# PCU_PCIe.net
KiCad netlist of a schematic drawn in Altium Designer
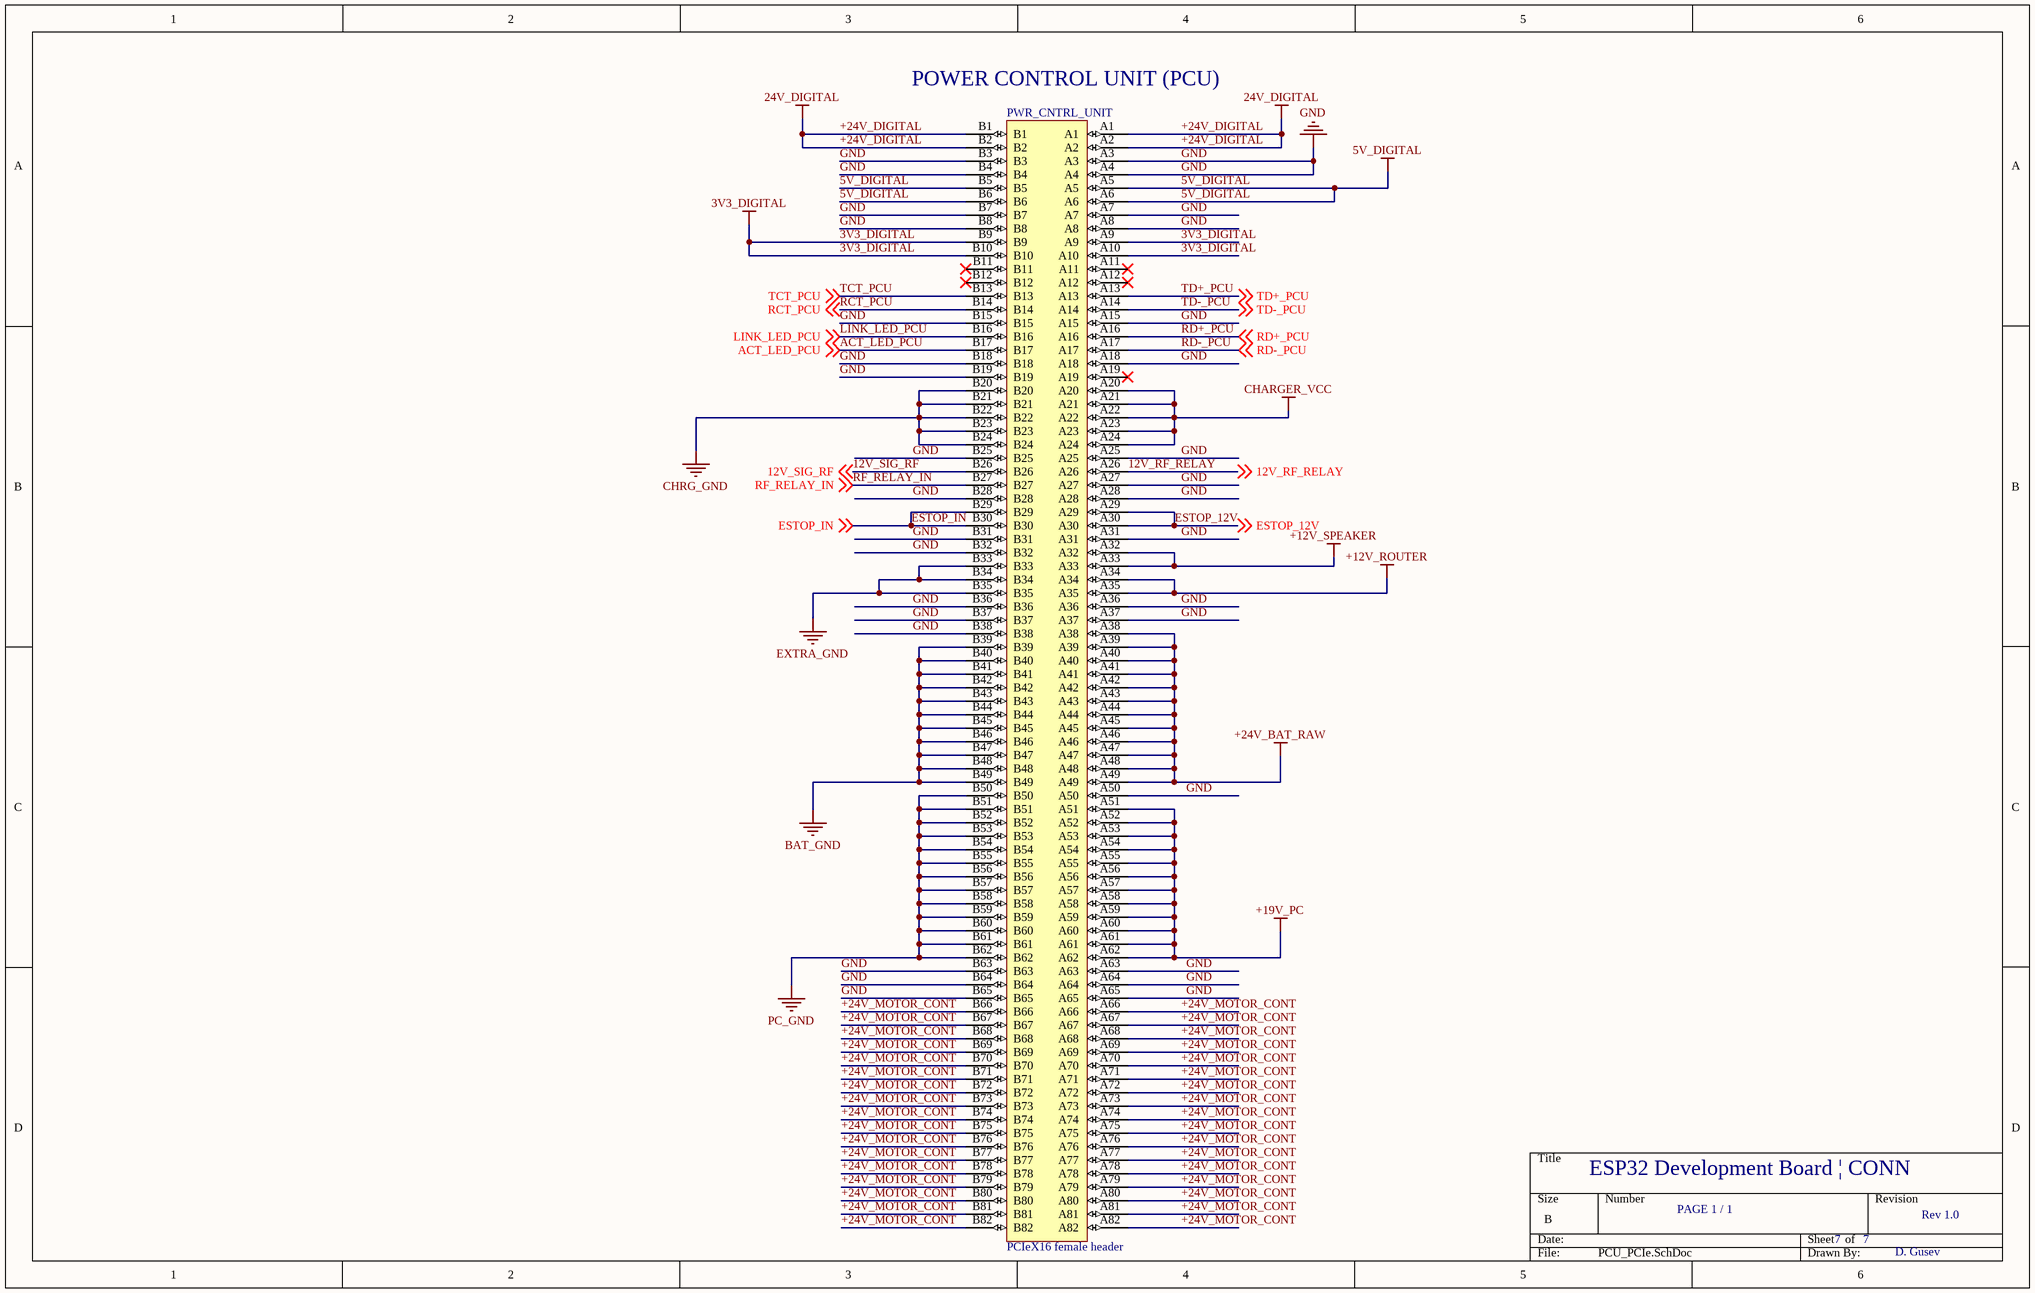
[diagram p0: PCU_PCIe.SchDoc]

(export (version "E")
  (design (tool "Eeschema 10.0.6"))
  (components
    (comp (ref "PWR_CNTRL_UNIT")
      (value "PCIeX16 female header")
      (footprint "SAMTEC_PCIE-164-02-X-D-TH")
      (description "164-position SAMTEC female header")
      (libsource (lib "ANTS-MotherBoard-B1") (part "PCIeX16 female header"))
    )
  )
  (nets
    (net (code "1") (name "+12V_ROUTER") (class "Default")
      (node (ref "PWR_CNTRL_UNIT") (pin "A34") (pinfunction "A34_A34") (pintype "bidirectional"))
      (node (ref "PWR_CNTRL_UNIT") (pin "A35") (pinfunction "A35_A35") (pintype "bidirectional"))
    )
    (net (code "2") (name "+12V_SPEAKER") (class "Default")
      (node (ref "PWR_CNTRL_UNIT") (pin "A32") (pinfunction "A32_A32") (pintype "bidirectional"))
      (node (ref "PWR_CNTRL_UNIT") (pin "A33") (pinfunction "A33_A33") (pintype "bidirectional"))
    )
    (net (code "3") (name "+19V_PC") (class "Default")
      (node (ref "PWR_CNTRL_UNIT") (pin "A51") (pinfunction "A51_A51") (pintype "bidirectional"))
      (node (ref "PWR_CNTRL_UNIT") (pin "A52") (pinfunction "A52_A52") (pintype "bidirectional"))
      (node (ref "PWR_CNTRL_UNIT") (pin "A53") (pinfunction "A53_A53") (pintype "bidirectional"))
      (node (ref "PWR_CNTRL_UNIT") (pin "A54") (pinfunction "A54_A54") (pintype "bidirectional"))
      (node (ref "PWR_CNTRL_UNIT") (pin "A55") (pinfunction "A55_A55") (pintype "bidirectional"))
      (node (ref "PWR_CNTRL_UNIT") (pin "A56") (pinfunction "A56_A56") (pintype "bidirectional"))
      (node (ref "PWR_CNTRL_UNIT") (pin "A57") (pinfunction "A57_A57") (pintype "bidirectional"))
      (node (ref "PWR_CNTRL_UNIT") (pin "A58") (pinfunction "A58_A58") (pintype "bidirectional"))
      (node (ref "PWR_CNTRL_UNIT") (pin "A59") (pinfunction "A59_A59") (pintype "bidirectional"))
      (node (ref "PWR_CNTRL_UNIT") (pin "A60") (pinfunction "A60_A60") (pintype "bidirectional"))
      (node (ref "PWR_CNTRL_UNIT") (pin "A61") (pinfunction "A61_A61") (pintype "bidirectional"))
      (node (ref "PWR_CNTRL_UNIT") (pin "A62") (pinfunction "A62_A62") (pintype "bidirectional"))
    )
    (net (code "4") (name "+24V_BAT_RAW") (class "Default")
      (node (ref "PWR_CNTRL_UNIT") (pin "A38") (pinfunction "A38_A38") (pintype "bidirectional"))
      (node (ref "PWR_CNTRL_UNIT") (pin "A39") (pinfunction "A39_A39") (pintype "bidirectional"))
      (node (ref "PWR_CNTRL_UNIT") (pin "A40") (pinfunction "A40_A40") (pintype "bidirectional"))
      (node (ref "PWR_CNTRL_UNIT") (pin "A41") (pinfunction "A41_A41") (pintype "bidirectional"))
      (node (ref "PWR_CNTRL_UNIT") (pin "A42") (pinfunction "A42_A42") (pintype "bidirectional"))
      (node (ref "PWR_CNTRL_UNIT") (pin "A43") (pinfunction "A43_A43") (pintype "bidirectional"))
      (node (ref "PWR_CNTRL_UNIT") (pin "A44") (pinfunction "A44_A44") (pintype "bidirectional"))
      (node (ref "PWR_CNTRL_UNIT") (pin "A45") (pinfunction "A45_A45") (pintype "bidirectional"))
      (node (ref "PWR_CNTRL_UNIT") (pin "A46") (pinfunction "A46_A46") (pintype "bidirectional"))
      (node (ref "PWR_CNTRL_UNIT") (pin "A47") (pinfunction "A47_A47") (pintype "bidirectional"))
      (node (ref "PWR_CNTRL_UNIT") (pin "A48") (pinfunction "A48_A48") (pintype "bidirectional"))
      (node (ref "PWR_CNTRL_UNIT") (pin "A49") (pinfunction "A49_A49") (pintype "bidirectional"))
    )
    (net (code "5") (name "/+24V_MOTOR_CONT") (class "Default")
      (node (ref "PWR_CNTRL_UNIT") (pin "A66") (pinfunction "A66_A66") (pintype "bidirectional"))
      (node (ref "PWR_CNTRL_UNIT") (pin "A67") (pinfunction "A67_A67") (pintype "bidirectional"))
      (node (ref "PWR_CNTRL_UNIT") (pin "A68") (pinfunction "A68_A68") (pintype "bidirectional"))
      (node (ref "PWR_CNTRL_UNIT") (pin "A69") (pinfunction "A69_A69") (pintype "bidirectional"))
      (node (ref "PWR_CNTRL_UNIT") (pin "A70") (pinfunction "A70_A70") (pintype "bidirectional"))
      (node (ref "PWR_CNTRL_UNIT") (pin "A71") (pinfunction "A71_A71") (pintype "bidirectional"))
      (node (ref "PWR_CNTRL_UNIT") (pin "A72") (pinfunction "A72_A72") (pintype "bidirectional"))
      (node (ref "PWR_CNTRL_UNIT") (pin "A73") (pinfunction "A73_A73") (pintype "bidirectional"))
      (node (ref "PWR_CNTRL_UNIT") (pin "A74") (pinfunction "A74_A74") (pintype "bidirectional"))
      (node (ref "PWR_CNTRL_UNIT") (pin "A75") (pinfunction "A75_A75") (pintype "bidirectional"))
      (node (ref "PWR_CNTRL_UNIT") (pin "A76") (pinfunction "A76_A76") (pintype "bidirectional"))
      (node (ref "PWR_CNTRL_UNIT") (pin "A77") (pinfunction "A77_A77") (pintype "bidirectional"))
      (node (ref "PWR_CNTRL_UNIT") (pin "A78") (pinfunction "A78_A78") (pintype "bidirectional"))
      (node (ref "PWR_CNTRL_UNIT") (pin "A79") (pinfunction "A79_A79") (pintype "bidirectional"))
      (node (ref "PWR_CNTRL_UNIT") (pin "A80") (pinfunction "A80_A80") (pintype "bidirectional"))
      (node (ref "PWR_CNTRL_UNIT") (pin "A81") (pinfunction "A81_A81") (pintype "bidirectional"))
      (node (ref "PWR_CNTRL_UNIT") (pin "A82") (pinfunction "A82_A82") (pintype "bidirectional"))
      (node (ref "PWR_CNTRL_UNIT") (pin "B66") (pinfunction "B66_B66") (pintype "bidirectional"))
      (node (ref "PWR_CNTRL_UNIT") (pin "B67") (pinfunction "B67_B67") (pintype "bidirectional"))
      (node (ref "PWR_CNTRL_UNIT") (pin "B68") (pinfunction "B68_B68") (pintype "bidirectional"))
      (node (ref "PWR_CNTRL_UNIT") (pin "B69") (pinfunction "B69_B69") (pintype "bidirectional"))
      (node (ref "PWR_CNTRL_UNIT") (pin "B70") (pinfunction "B70_B70") (pintype "bidirectional"))
      (node (ref "PWR_CNTRL_UNIT") (pin "B71") (pinfunction "B71_B71") (pintype "bidirectional"))
      (node (ref "PWR_CNTRL_UNIT") (pin "B72") (pinfunction "B72_B72") (pintype "bidirectional"))
      (node (ref "PWR_CNTRL_UNIT") (pin "B73") (pinfunction "B73_B73") (pintype "bidirectional"))
      (node (ref "PWR_CNTRL_UNIT") (pin "B74") (pinfunction "B74_B74") (pintype "bidirectional"))
      (node (ref "PWR_CNTRL_UNIT") (pin "B75") (pinfunction "B75_B75") (pintype "bidirectional"))
      (node (ref "PWR_CNTRL_UNIT") (pin "B76") (pinfunction "B76_B76") (pintype "bidirectional"))
      (node (ref "PWR_CNTRL_UNIT") (pin "B77") (pinfunction "B77_B77") (pintype "bidirectional"))
      (node (ref "PWR_CNTRL_UNIT") (pin "B78") (pinfunction "B78_B78") (pintype "bidirectional"))
      (node (ref "PWR_CNTRL_UNIT") (pin "B79") (pinfunction "B79_B79") (pintype "bidirectional"))
      (node (ref "PWR_CNTRL_UNIT") (pin "B80") (pinfunction "B80_B80") (pintype "bidirectional"))
      (node (ref "PWR_CNTRL_UNIT") (pin "B81") (pinfunction "B81_B81") (pintype "bidirectional"))
      (node (ref "PWR_CNTRL_UNIT") (pin "B82") (pinfunction "B82_B82") (pintype "bidirectional"))
    )
    (net (code "6") (name "3V3_DIGITAL") (class "Default")
      (node (ref "PWR_CNTRL_UNIT") (pin "A10") (pinfunction "A10_A10") (pintype "bidirectional"))
      (node (ref "PWR_CNTRL_UNIT") (pin "A9") (pinfunction "A9_A9") (pintype "bidirectional"))
      (node (ref "PWR_CNTRL_UNIT") (pin "B10") (pinfunction "B10_B10") (pintype "bidirectional"))
      (node (ref "PWR_CNTRL_UNIT") (pin "B9") (pinfunction "B9_B9") (pintype "bidirectional"))
    )
    (net (code "7") (name "5V_DIGITAL") (class "Default")
      (node (ref "PWR_CNTRL_UNIT") (pin "A5") (pinfunction "A5_A5") (pintype "bidirectional"))
      (node (ref "PWR_CNTRL_UNIT") (pin "A6") (pinfunction "A6_A6") (pintype "bidirectional"))
      (node (ref "PWR_CNTRL_UNIT") (pin "B5") (pinfunction "B5_B5") (pintype "bidirectional"))
      (node (ref "PWR_CNTRL_UNIT") (pin "B6") (pinfunction "B6_B6") (pintype "bidirectional"))
    )
    (net (code "8") (name "12V_RF_RELAY") (class "Default")
      (node (ref "PWR_CNTRL_UNIT") (pin "A26") (pinfunction "A26_A26") (pintype "bidirectional"))
    )
    (net (code "9") (name "12V_SIG_RF") (class "Default")
      (node (ref "PWR_CNTRL_UNIT") (pin "B26") (pinfunction "B26_B26") (pintype "bidirectional"))
    )
    (net (code "10") (name "24V_DIGITAL") (class "Default")
      (node (ref "PWR_CNTRL_UNIT") (pin "A1") (pinfunction "A1_A1") (pintype "bidirectional"))
      (node (ref "PWR_CNTRL_UNIT") (pin "A2") (pinfunction "A2_A2") (pintype "bidirectional"))
      (node (ref "PWR_CNTRL_UNIT") (pin "B1") (pinfunction "B1_B1") (pintype "bidirectional"))
      (node (ref "PWR_CNTRL_UNIT") (pin "B2") (pinfunction "B2_B2") (pintype "bidirectional"))
    )
    (net (code "11") (name "ACT_LED_PCU") (class "Default")
      (node (ref "PWR_CNTRL_UNIT") (pin "B17") (pinfunction "B17_B17") (pintype "bidirectional"))
    )
    (net (code "12") (name "BAT_GND") (class "Default")
      (node (ref "PWR_CNTRL_UNIT") (pin "B39") (pinfunction "B39_B39") (pintype "bidirectional"))
      (node (ref "PWR_CNTRL_UNIT") (pin "B40") (pinfunction "B40_B40") (pintype "bidirectional"))
      (node (ref "PWR_CNTRL_UNIT") (pin "B41") (pinfunction "B41_B41") (pintype "bidirectional"))
      (node (ref "PWR_CNTRL_UNIT") (pin "B42") (pinfunction "B42_B42") (pintype "bidirectional"))
      (node (ref "PWR_CNTRL_UNIT") (pin "B43") (pinfunction "B43_B43") (pintype "bidirectional"))
      (node (ref "PWR_CNTRL_UNIT") (pin "B44") (pinfunction "B44_B44") (pintype "bidirectional"))
      (node (ref "PWR_CNTRL_UNIT") (pin "B45") (pinfunction "B45_B45") (pintype "bidirectional"))
      (node (ref "PWR_CNTRL_UNIT") (pin "B46") (pinfunction "B46_B46") (pintype "bidirectional"))
      (node (ref "PWR_CNTRL_UNIT") (pin "B47") (pinfunction "B47_B47") (pintype "bidirectional"))
      (node (ref "PWR_CNTRL_UNIT") (pin "B48") (pinfunction "B48_B48") (pintype "bidirectional"))
      (node (ref "PWR_CNTRL_UNIT") (pin "B49") (pinfunction "B49_B49") (pintype "bidirectional"))
    )
    (net (code "13") (name "CHARGER_VCC") (class "Default")
      (node (ref "PWR_CNTRL_UNIT") (pin "A20") (pinfunction "A20_A20") (pintype "bidirectional"))
      (node (ref "PWR_CNTRL_UNIT") (pin "A21") (pinfunction "A21_A21") (pintype "bidirectional"))
      (node (ref "PWR_CNTRL_UNIT") (pin "A22") (pinfunction "A22_A22") (pintype "bidirectional"))
      (node (ref "PWR_CNTRL_UNIT") (pin "A23") (pinfunction "A23_A23") (pintype "bidirectional"))
      (node (ref "PWR_CNTRL_UNIT") (pin "A24") (pinfunction "A24_A24") (pintype "bidirectional"))
    )
    (net (code "14") (name "CHRG_GND") (class "Default")
      (node (ref "PWR_CNTRL_UNIT") (pin "B20") (pinfunction "B20_B20") (pintype "bidirectional"))
      (node (ref "PWR_CNTRL_UNIT") (pin "B21") (pinfunction "B21_B21") (pintype "bidirectional"))
      (node (ref "PWR_CNTRL_UNIT") (pin "B22") (pinfunction "B22_B22") (pintype "bidirectional"))
      (node (ref "PWR_CNTRL_UNIT") (pin "B23") (pinfunction "B23_B23") (pintype "bidirectional"))
      (node (ref "PWR_CNTRL_UNIT") (pin "B24") (pinfunction "B24_B24") (pintype "bidirectional"))
    )
    (net (code "15") (name "ESTOP_12V") (class "Default")
      (node (ref "PWR_CNTRL_UNIT") (pin "A29") (pinfunction "A29_A29") (pintype "bidirectional"))
      (node (ref "PWR_CNTRL_UNIT") (pin "A30") (pinfunction "A30_A30") (pintype "bidirectional"))
    )
    (net (code "16") (name "ESTOP_IN") (class "Default")
      (node (ref "PWR_CNTRL_UNIT") (pin "B29") (pinfunction "B29_B29") (pintype "bidirectional"))
      (node (ref "PWR_CNTRL_UNIT") (pin "B30") (pinfunction "B30_B30") (pintype "bidirectional"))
    )
    (net (code "17") (name "EXTRA_GND") (class "Default")
      (node (ref "PWR_CNTRL_UNIT") (pin "B33") (pinfunction "B33_B33") (pintype "bidirectional"))
      (node (ref "PWR_CNTRL_UNIT") (pin "B34") (pinfunction "B34_B34") (pintype "bidirectional"))
      (node (ref "PWR_CNTRL_UNIT") (pin "B35") (pinfunction "B35_B35") (pintype "bidirectional"))
    )
    (net (code "18") (name "GND") (class "Default")
      (node (ref "PWR_CNTRL_UNIT") (pin "A15") (pinfunction "A15_A15") (pintype "bidirectional"))
      (node (ref "PWR_CNTRL_UNIT") (pin "A18") (pinfunction "A18_A18") (pintype "bidirectional"))
      (node (ref "PWR_CNTRL_UNIT") (pin "A25") (pinfunction "A25_A25") (pintype "bidirectional"))
      (node (ref "PWR_CNTRL_UNIT") (pin "A27") (pinfunction "A27_A27") (pintype "bidirectional"))
      (node (ref "PWR_CNTRL_UNIT") (pin "A28") (pinfunction "A28_A28") (pintype "bidirectional"))
      (node (ref "PWR_CNTRL_UNIT") (pin "A3") (pinfunction "A3_A3") (pintype "bidirectional"))
      (node (ref "PWR_CNTRL_UNIT") (pin "A31") (pinfunction "A31_A31") (pintype "bidirectional"))
      (node (ref "PWR_CNTRL_UNIT") (pin "A36") (pinfunction "A36_A36") (pintype "bidirectional"))
      (node (ref "PWR_CNTRL_UNIT") (pin "A37") (pinfunction "A37_A37") (pintype "bidirectional"))
      (node (ref "PWR_CNTRL_UNIT") (pin "A4") (pinfunction "A4_A4") (pintype "bidirectional"))
      (node (ref "PWR_CNTRL_UNIT") (pin "A50") (pinfunction "A50_A50") (pintype "bidirectional"))
      (node (ref "PWR_CNTRL_UNIT") (pin "A63") (pinfunction "A63_A63") (pintype "bidirectional"))
      (node (ref "PWR_CNTRL_UNIT") (pin "A64") (pinfunction "A64_A64") (pintype "bidirectional"))
      (node (ref "PWR_CNTRL_UNIT") (pin "A65") (pinfunction "A65_A65") (pintype "bidirectional"))
      (node (ref "PWR_CNTRL_UNIT") (pin "A7") (pinfunction "A7_A7") (pintype "bidirectional"))
      (node (ref "PWR_CNTRL_UNIT") (pin "A8") (pinfunction "A8_A8") (pintype "bidirectional"))
      (node (ref "PWR_CNTRL_UNIT") (pin "B15") (pinfunction "B15_B15") (pintype "bidirectional"))
      (node (ref "PWR_CNTRL_UNIT") (pin "B18") (pinfunction "B18_B18") (pintype "bidirectional"))
      (node (ref "PWR_CNTRL_UNIT") (pin "B19") (pinfunction "B19_B19") (pintype "bidirectional"))
      (node (ref "PWR_CNTRL_UNIT") (pin "B25") (pinfunction "B25_B25") (pintype "bidirectional"))
      (node (ref "PWR_CNTRL_UNIT") (pin "B28") (pinfunction "B28_B28") (pintype "bidirectional"))
      (node (ref "PWR_CNTRL_UNIT") (pin "B3") (pinfunction "B3_B3") (pintype "bidirectional"))
      (node (ref "PWR_CNTRL_UNIT") (pin "B31") (pinfunction "B31_B31") (pintype "bidirectional"))
      (node (ref "PWR_CNTRL_UNIT") (pin "B32") (pinfunction "B32_B32") (pintype "bidirectional"))
      (node (ref "PWR_CNTRL_UNIT") (pin "B36") (pinfunction "B36_B36") (pintype "bidirectional"))
      (node (ref "PWR_CNTRL_UNIT") (pin "B37") (pinfunction "B37_B37") (pintype "bidirectional"))
      (node (ref "PWR_CNTRL_UNIT") (pin "B38") (pinfunction "B38_B38") (pintype "bidirectional"))
      (node (ref "PWR_CNTRL_UNIT") (pin "B4") (pinfunction "B4_B4") (pintype "bidirectional"))
      (node (ref "PWR_CNTRL_UNIT") (pin "B63") (pinfunction "B63_B63") (pintype "bidirectional"))
      (node (ref "PWR_CNTRL_UNIT") (pin "B64") (pinfunction "B64_B64") (pintype "bidirectional"))
      (node (ref "PWR_CNTRL_UNIT") (pin "B65") (pinfunction "B65_B65") (pintype "bidirectional"))
      (node (ref "PWR_CNTRL_UNIT") (pin "B7") (pinfunction "B7_B7") (pintype "bidirectional"))
      (node (ref "PWR_CNTRL_UNIT") (pin "B8") (pinfunction "B8_B8") (pintype "bidirectional"))
    )
    (net (code "19") (name "LINK_LED_PCU") (class "Default")
      (node (ref "PWR_CNTRL_UNIT") (pin "B16") (pinfunction "B16_B16") (pintype "bidirectional"))
    )
    (net (code "20") (name "PC_GND") (class "Default")
      (node (ref "PWR_CNTRL_UNIT") (pin "B50") (pinfunction "B50_B50") (pintype "bidirectional"))
      (node (ref "PWR_CNTRL_UNIT") (pin "B51") (pinfunction "B51_B51") (pintype "bidirectional"))
      (node (ref "PWR_CNTRL_UNIT") (pin "B52") (pinfunction "B52_B52") (pintype "bidirectional"))
      (node (ref "PWR_CNTRL_UNIT") (pin "B53") (pinfunction "B53_B53") (pintype "bidirectional"))
      (node (ref "PWR_CNTRL_UNIT") (pin "B54") (pinfunction "B54_B54") (pintype "bidirectional"))
      (node (ref "PWR_CNTRL_UNIT") (pin "B55") (pinfunction "B55_B55") (pintype "bidirectional"))
      (node (ref "PWR_CNTRL_UNIT") (pin "B56") (pinfunction "B56_B56") (pintype "bidirectional"))
      (node (ref "PWR_CNTRL_UNIT") (pin "B57") (pinfunction "B57_B57") (pintype "bidirectional"))
      (node (ref "PWR_CNTRL_UNIT") (pin "B58") (pinfunction "B58_B58") (pintype "bidirectional"))
      (node (ref "PWR_CNTRL_UNIT") (pin "B59") (pinfunction "B59_B59") (pintype "bidirectional"))
      (node (ref "PWR_CNTRL_UNIT") (pin "B60") (pinfunction "B60_B60") (pintype "bidirectional"))
      (node (ref "PWR_CNTRL_UNIT") (pin "B61") (pinfunction "B61_B61") (pintype "bidirectional"))
      (node (ref "PWR_CNTRL_UNIT") (pin "B62") (pinfunction "B62_B62") (pintype "bidirectional"))
    )
    (net (code "21") (name "RCT_PCU") (class "Default")
      (node (ref "PWR_CNTRL_UNIT") (pin "B14") (pinfunction "B14_B14") (pintype "bidirectional"))
    )
    (net (code "22") (name "RD+_PCU") (class "Default")
      (node (ref "PWR_CNTRL_UNIT") (pin "A16") (pinfunction "A16_A16") (pintype "bidirectional"))
    )
    (net (code "23") (name "RD-_PCU") (class "Default")
      (node (ref "PWR_CNTRL_UNIT") (pin "A17") (pinfunction "A17_A17") (pintype "bidirectional"))
    )
    (net (code "24") (name "RF_RELAY_IN") (class "Default")
      (node (ref "PWR_CNTRL_UNIT") (pin "B27") (pinfunction "B27_B27") (pintype "bidirectional"))
    )
    (net (code "25") (name "TCT_PCU") (class "Default")
      (node (ref "PWR_CNTRL_UNIT") (pin "B13") (pinfunction "B13_B13") (pintype "bidirectional"))
    )
    (net (code "26") (name "TD+_PCU") (class "Default")
      (node (ref "PWR_CNTRL_UNIT") (pin "A13") (pinfunction "A13_A13") (pintype "bidirectional"))
    )
    (net (code "27") (name "TD-_PCU") (class "Default")
      (node (ref "PWR_CNTRL_UNIT") (pin "A14") (pinfunction "A14_A14") (pintype "bidirectional"))
    )
    (net (code "28") (name "unconnected-(PWR_CNTRL_UNIT-PadA11)") (class "Default")
      (node (ref "PWR_CNTRL_UNIT") (pin "A11") (pinfunction "A11_A11") (pintype "bidirectional+no_connect"))
    )
    (net (code "29") (name "unconnected-(PWR_CNTRL_UNIT-PadA12)") (class "Default")
      (node (ref "PWR_CNTRL_UNIT") (pin "A12") (pinfunction "A12_A12") (pintype "bidirectional+no_connect"))
    )
    (net (code "30") (name "unconnected-(PWR_CNTRL_UNIT-PadA19)") (class "Default")
      (node (ref "PWR_CNTRL_UNIT") (pin "A19") (pinfunction "A19_A19") (pintype "bidirectional+no_connect"))
    )
    (net (code "31") (name "unconnected-(PWR_CNTRL_UNIT-PadB11)") (class "Default")
      (node (ref "PWR_CNTRL_UNIT") (pin "B11") (pinfunction "B11_B11") (pintype "bidirectional+no_connect"))
    )
    (net (code "32") (name "unconnected-(PWR_CNTRL_UNIT-PadB12)") (class "Default")
      (node (ref "PWR_CNTRL_UNIT") (pin "B12") (pinfunction "B12_B12") (pintype "bidirectional+no_connect"))
    )
  )
)
